# automaton.net
KiCad netlist of a schematic drawn in EAGLE
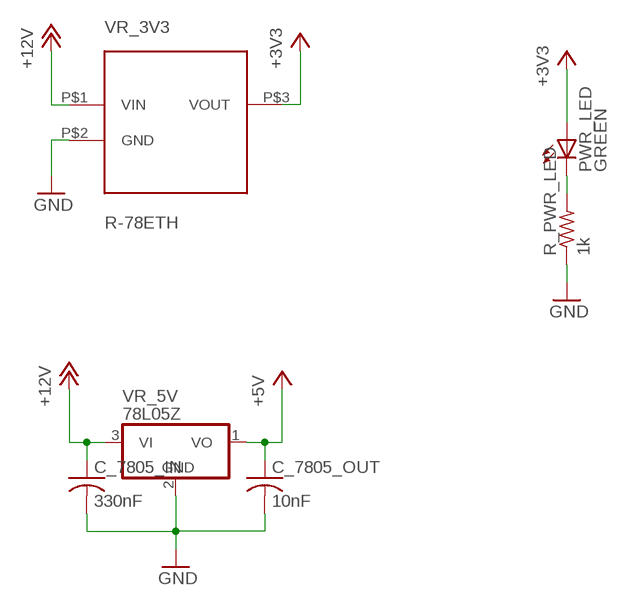
[diagram p0: schematic, sheet 1]
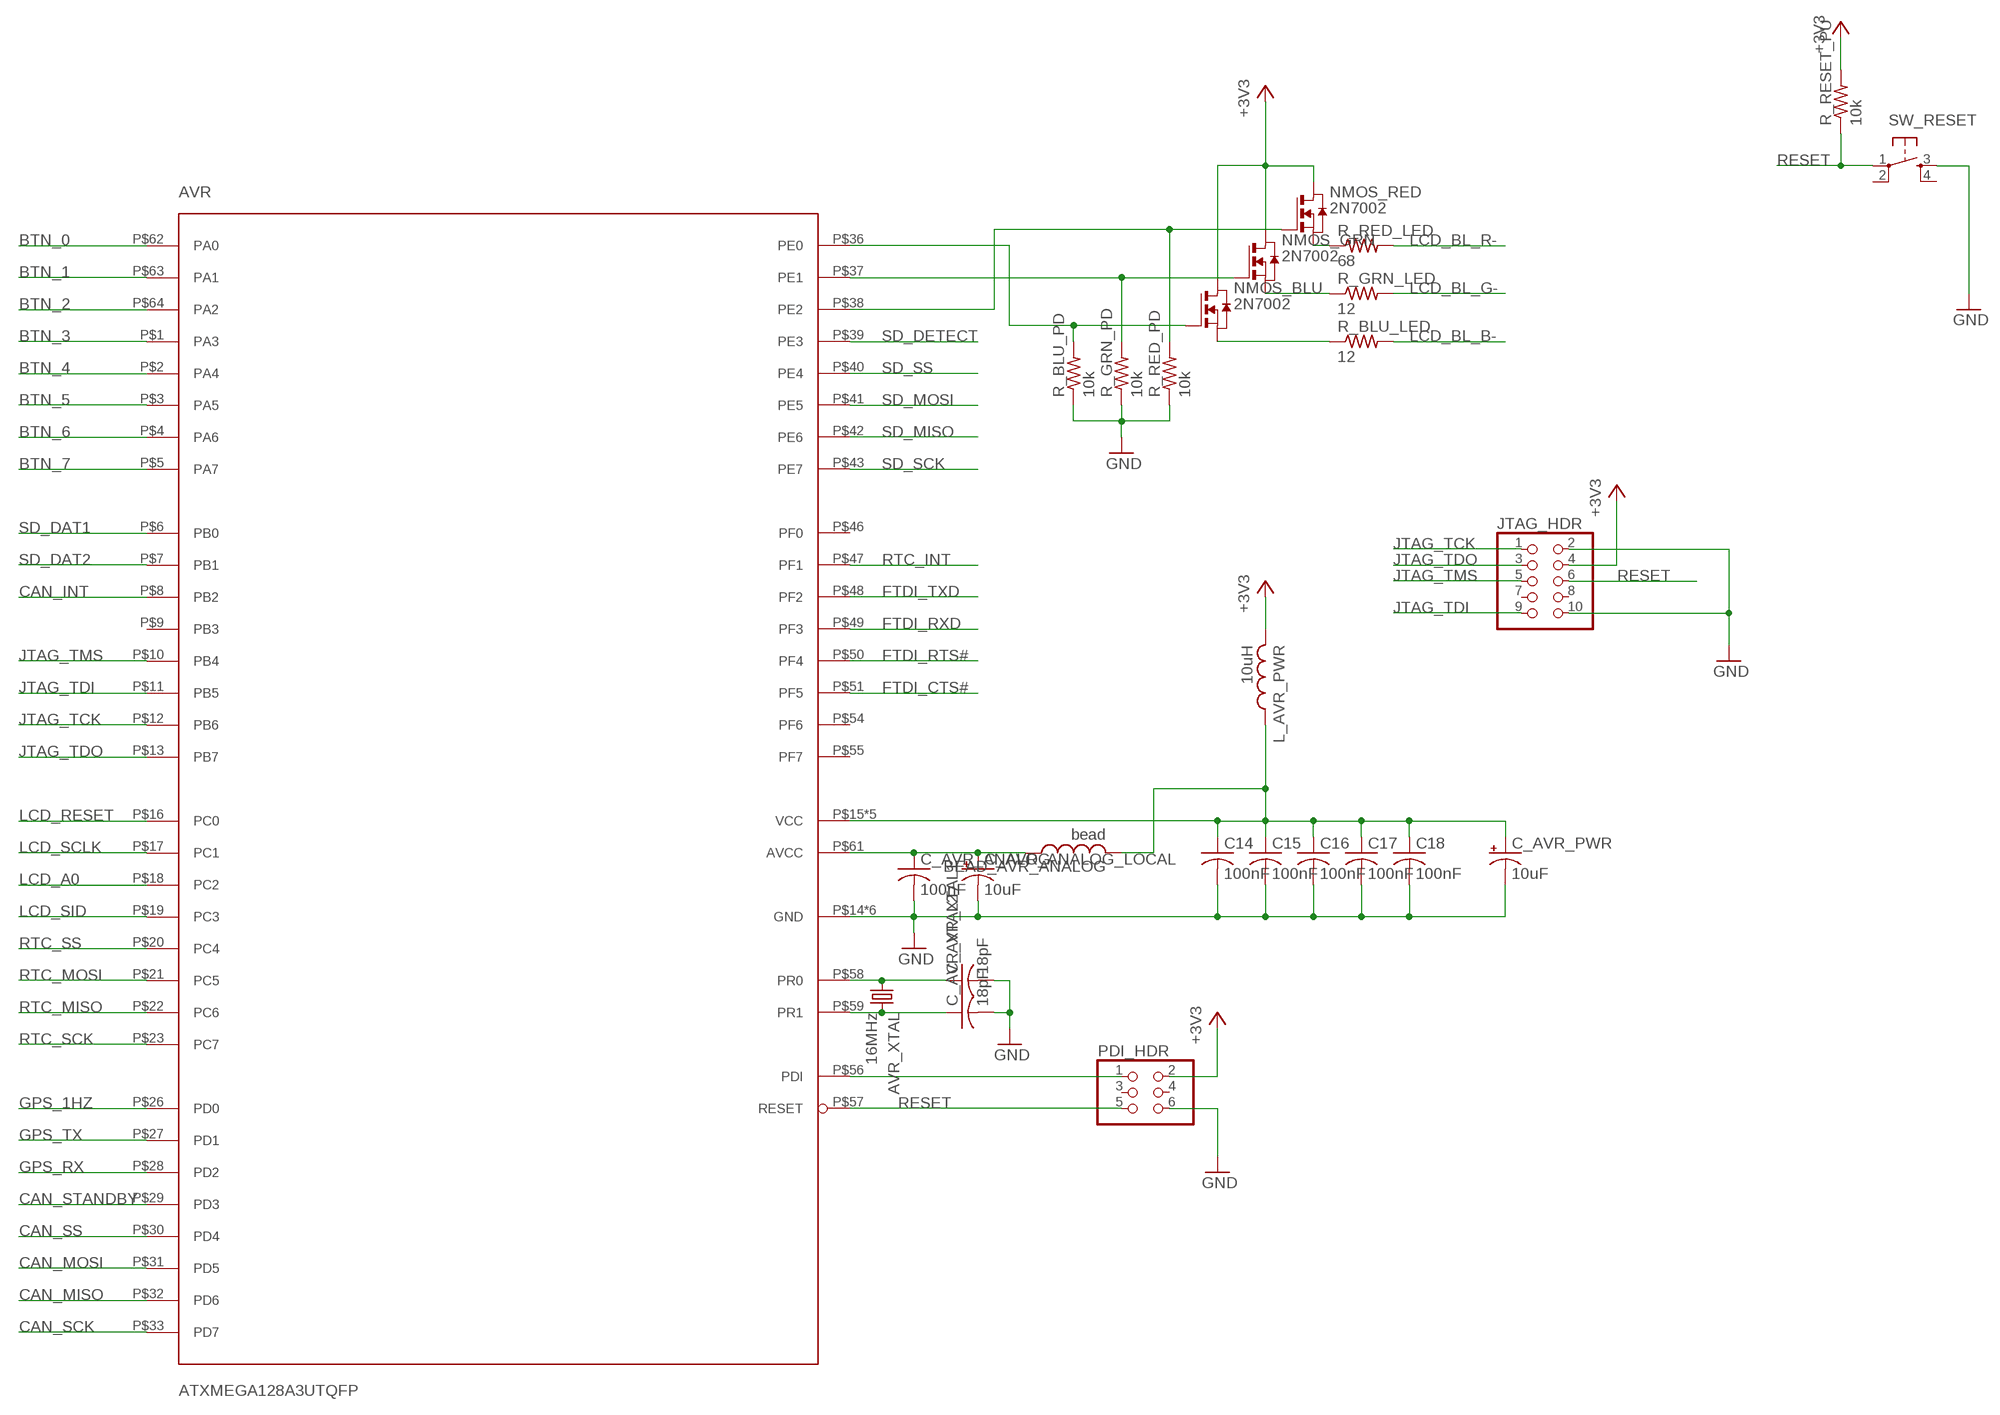
[diagram p1: schematic, sheet 2]
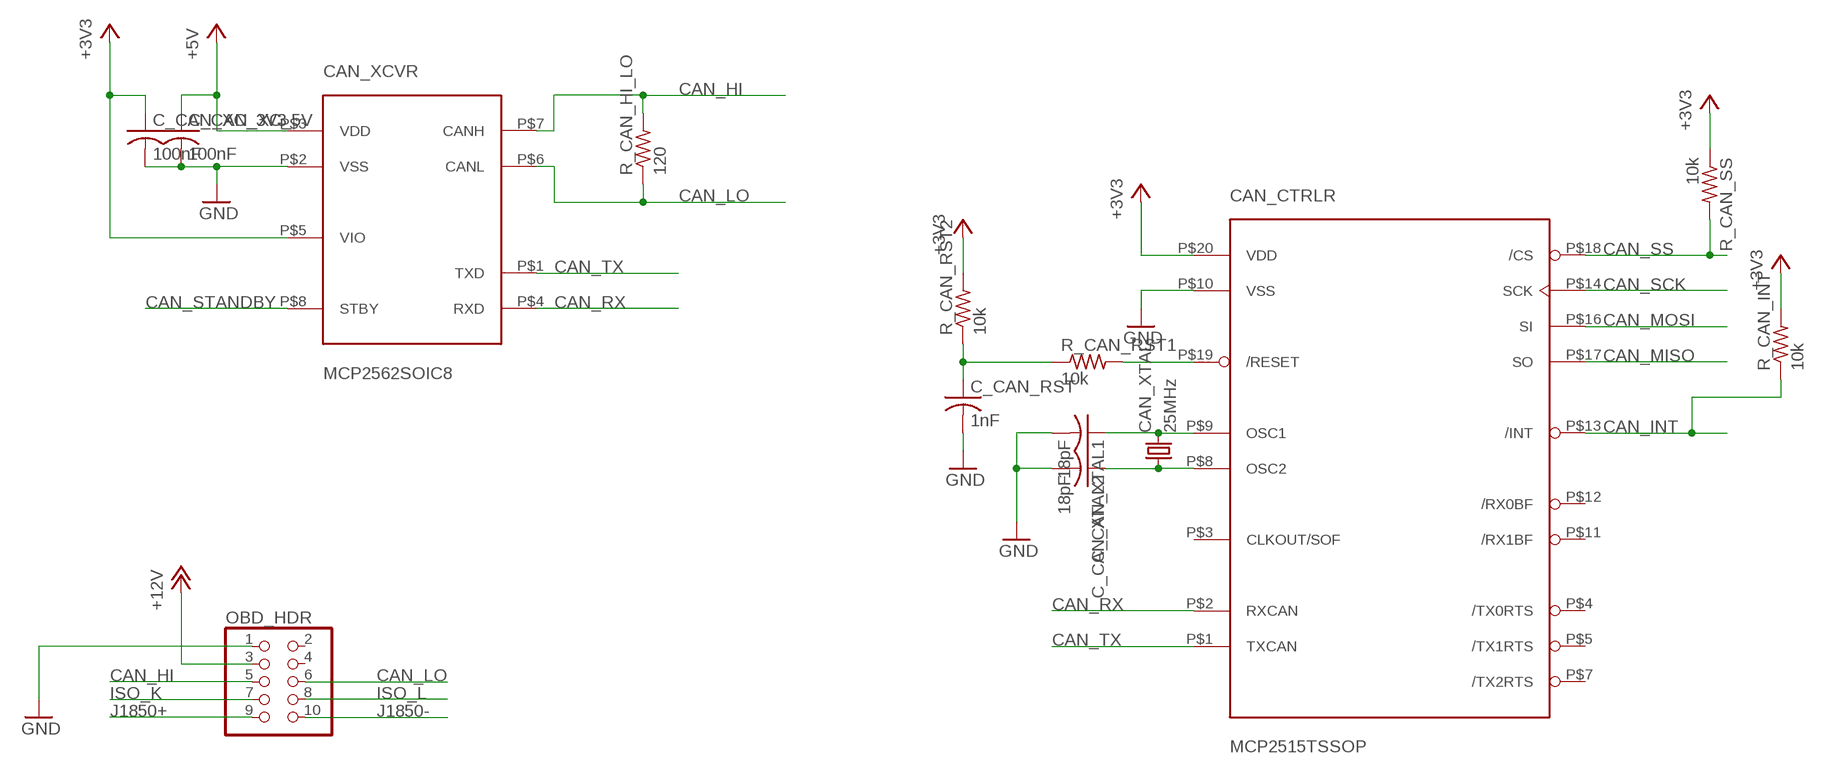
[diagram p2: schematic, sheet 3]
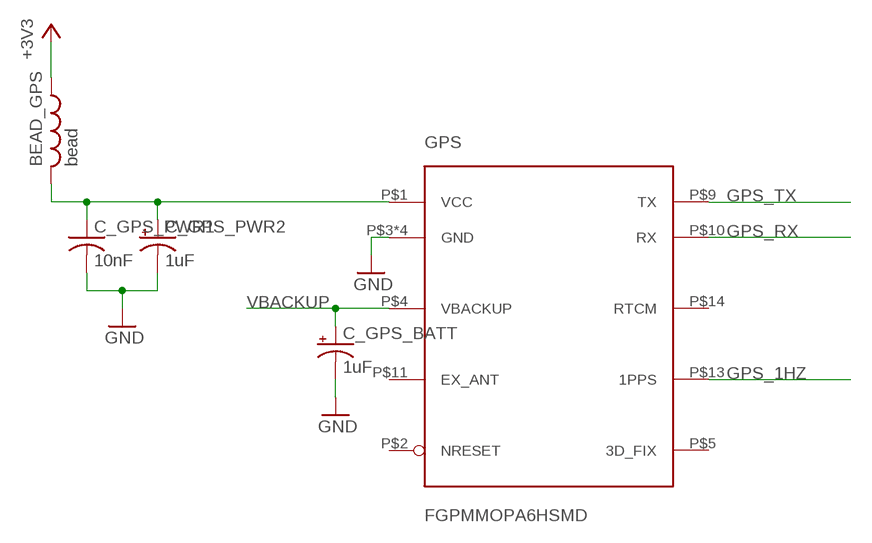
[diagram p3: schematic, sheet 4]
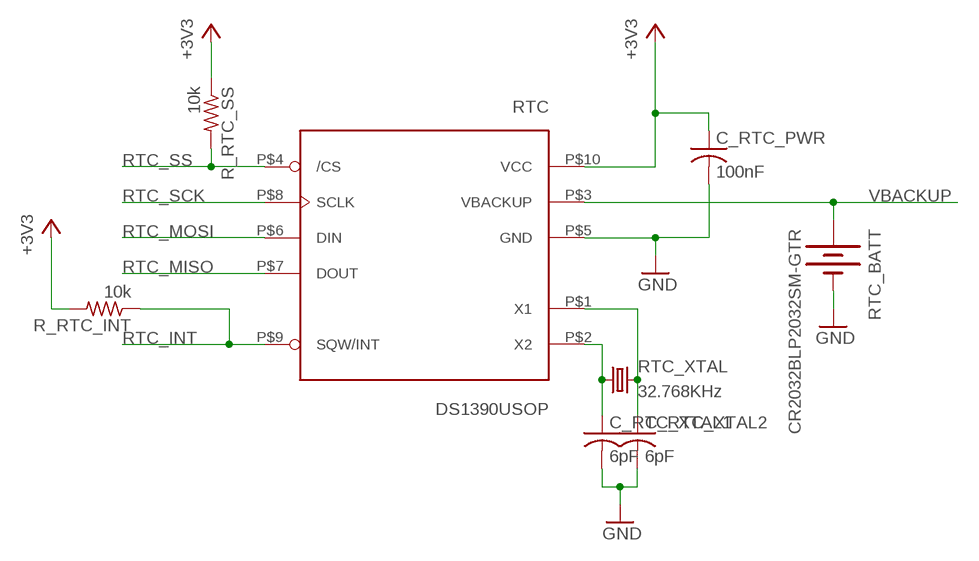
[diagram p4: schematic, sheet 5]
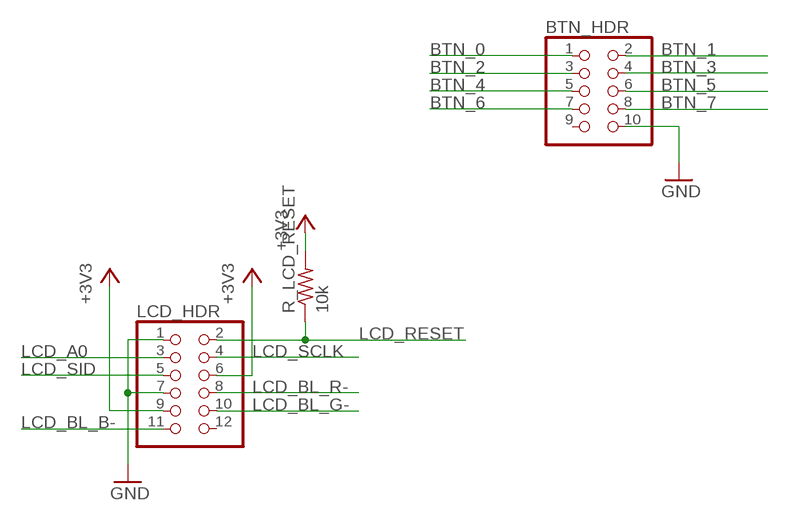
[diagram p5: schematic, sheet 6]
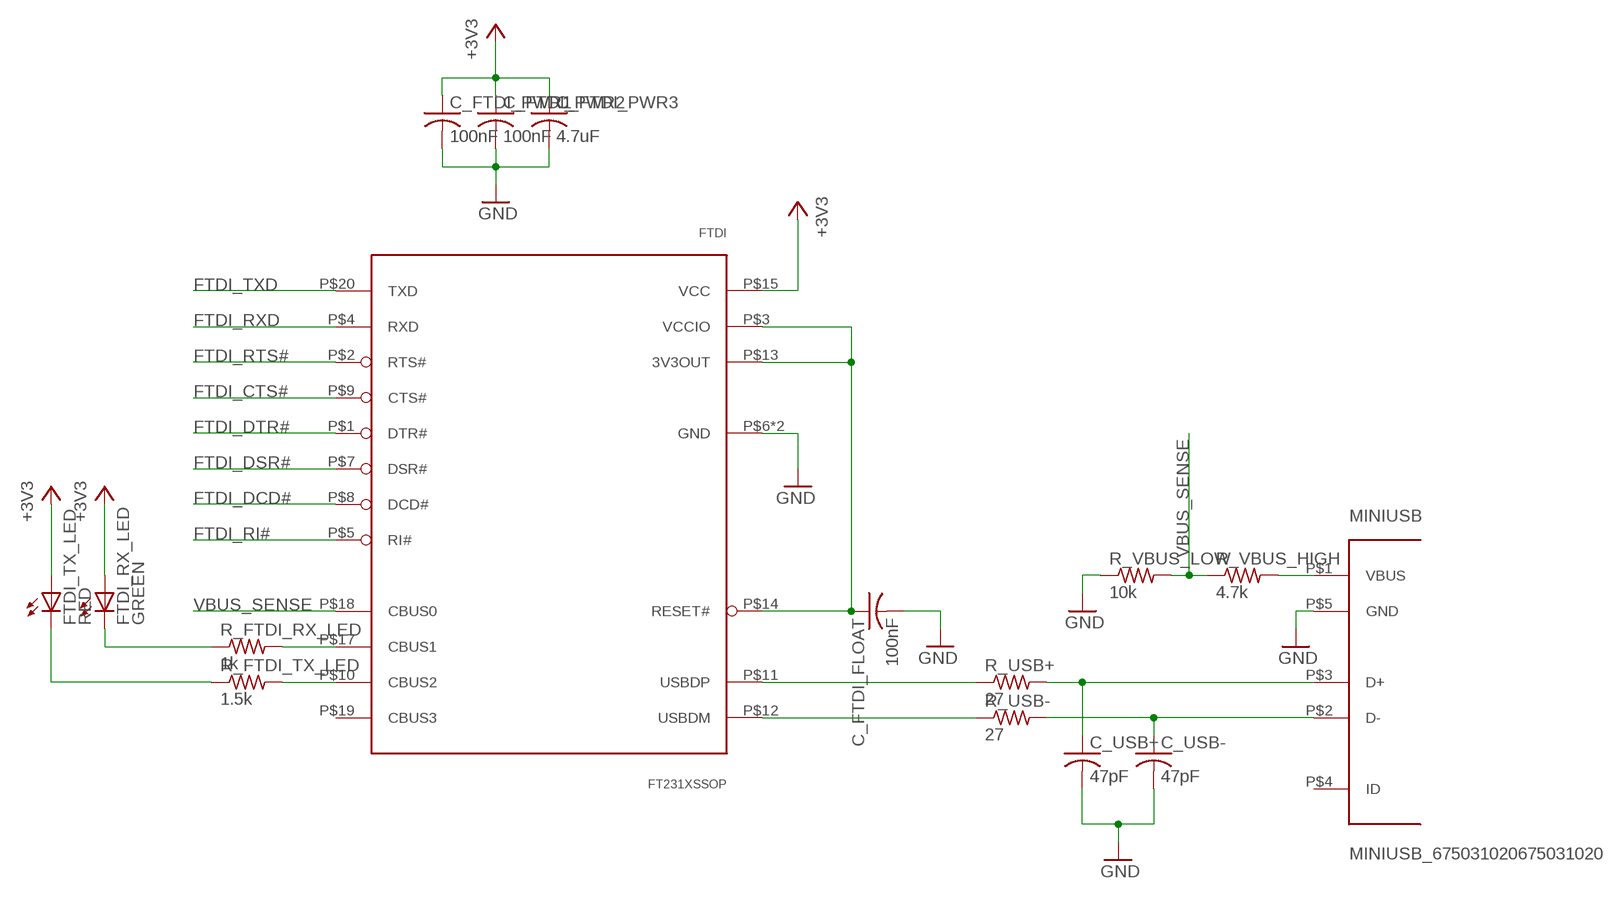
[diagram p6: schematic, sheet 7]
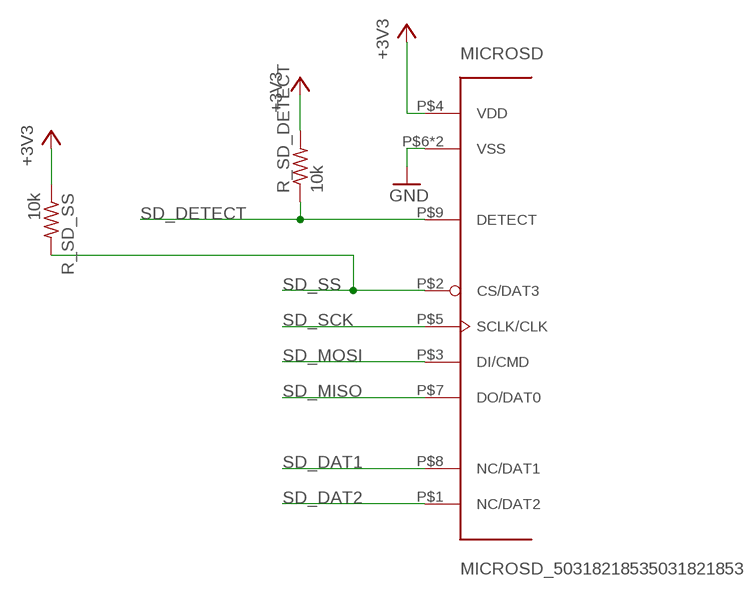
[diagram p7: schematic, sheet 8]

(export (version "E")
  (design (tool "Eeschema 10.0.6"))
  (components
    (comp (ref "MICROSD")
      (value "MICROSD_50318218535031821853")
      (footprint "eagle-import:MICROSD_5031821853")
      (libsource (lib "eagle-import") (part "MICROSD_50318218535031821853"))
    )
    (comp (ref "R_SD_DETECT")
      (value "10k")
      (footprint "eagle-import:R1206")
      (libsource (lib "eagle-import") (part "R-US_R1206"))
    )
    (comp (ref "R_SD_SS")
      (value "10k")
      (footprint "eagle-import:R1206")
      (libsource (lib "eagle-import") (part "R-US_R1206"))
    )
    (comp (ref "BEAD_GPS")
      (value "bead")
      (footprint "eagle-import:L1812")
      (libsource (lib "eagle-import") (part "L-USL1812"))
    )
    (comp (ref "C_GPS_BATT")
      (value "1uF")
      (footprint "eagle-import:E2-5")
      (libsource (lib "eagle-import") (part "CPOL-USE2-5"))
    )
    (comp (ref "C_GPS_PWR1")
      (value "10nF")
      (footprint "eagle-import:C1206")
      (libsource (lib "eagle-import") (part "C-USC1206"))
    )
    (comp (ref "C_GPS_PWR2")
      (value "1uF")
      (footprint "eagle-import:E2-5")
      (libsource (lib "eagle-import") (part "CPOL-USE2-5"))
    )
    (comp (ref "GPS")
      (value "FGPMMOPA6HSMD")
      (footprint "eagle-import:FGPMMOPA6H")
      (libsource (lib "eagle-import") (part "FGPMMOPA6HSMD"))
    )
    (comp (ref "AVR")
      (value "ATXMEGA128A3UTQFP")
      (footprint "eagle-import:ATMEL_TQFP64")
      (libsource (lib "eagle-import") (part "ATXMEGA128A3UTQFP"))
    )
    (comp (ref "AVR_XTAL")
      (value "16MHz")
      (footprint "eagle-import:HC49_S")
      (libsource (lib "eagle-import") (part "CRYSTALHC49S"))
    )
    (comp (ref "BEAD_AVR_ANALOG")
      (value "bead")
      (footprint "eagle-import:L1812")
      (libsource (lib "eagle-import") (part "L-USL1812"))
    )
    (comp (ref "C14")
      (value "100nF")
      (footprint "eagle-import:C1206")
      (libsource (lib "eagle-import") (part "C-USC1206"))
    )
    (comp (ref "C15")
      (value "100nF")
      (footprint "eagle-import:C1206")
      (libsource (lib "eagle-import") (part "C-USC1206"))
    )
    (comp (ref "C16")
      (value "100nF")
      (footprint "eagle-import:C1206")
      (libsource (lib "eagle-import") (part "C-USC1206"))
    )
    (comp (ref "C17")
      (value "100nF")
      (footprint "eagle-import:C1206")
      (libsource (lib "eagle-import") (part "C-USC1206"))
    )
    (comp (ref "C18")
      (value "100nF")
      (footprint "eagle-import:C1206")
      (libsource (lib "eagle-import") (part "C-USC1206"))
    )
    (comp (ref "C_AVR_ANALOG")
      (value "100nF")
      (footprint "eagle-import:C1206")
      (libsource (lib "eagle-import") (part "C-USC1206"))
    )
    (comp (ref "C_AVR_ANALOG_LOCAL")
      (value "10uF")
      (footprint "eagle-import:E2-5")
      (libsource (lib "eagle-import") (part "CPOL-USE2-5"))
    )
    (comp (ref "C_AVR_PWR")
      (value "10uF")
      (footprint "eagle-import:E2-5")
      (libsource (lib "eagle-import") (part "CPOL-USE2-5"))
    )
    (comp (ref "C_AVR_XTAL1")
      (value "18pF")
      (footprint "eagle-import:C1206")
      (libsource (lib "eagle-import") (part "C-USC1206"))
    )
    (comp (ref "C_AVR_XTAL2")
      (value "18pF")
      (footprint "eagle-import:C1206")
      (libsource (lib "eagle-import") (part "C-USC1206"))
    )
    (comp (ref "JTAG_HDR")
      (value "PINHD-2X05_2.54")
      (footprint "eagle-import:2X05")
      (libsource (lib "eagle-import") (part "PINHD-2X05_2.54"))
    )
    (comp (ref "L_AVR_PWR")
      (value "10uH")
      (footprint "eagle-import:L1812")
      (libsource (lib "eagle-import") (part "L-USL1812"))
    )
    (comp (ref "NMOS_BLU")
      (value "2N7002")
      (footprint "eagle-import:SOT-23")
      (libsource (lib "eagle-import") (part "NMOSSOT23"))
    )
    (comp (ref "NMOS_GRN")
      (value "2N7002")
      (footprint "eagle-import:SOT-23")
      (libsource (lib "eagle-import") (part "NMOSSOT23"))
    )
    (comp (ref "NMOS_RED")
      (value "2N7002")
      (footprint "eagle-import:SOT-23")
      (libsource (lib "eagle-import") (part "NMOSSOT23"))
    )
    (comp (ref "PDI_HDR")
      (value "PINHD-2X03_2.54")
      (footprint "eagle-import:2X03")
      (libsource (lib "eagle-import") (part "PINHD-2X03_2.54"))
    )
    (comp (ref "R_BLU_LED")
      (value "12")
      (footprint "eagle-import:R1206")
      (libsource (lib "eagle-import") (part "R-US_R1206"))
    )
    (comp (ref "R_BLU_PD")
      (value "10k")
      (footprint "eagle-import:R1206")
      (libsource (lib "eagle-import") (part "R-US_R1206"))
    )
    (comp (ref "R_GRN_LED")
      (value "12")
      (footprint "eagle-import:R1206")
      (libsource (lib "eagle-import") (part "R-US_R1206"))
    )
    (comp (ref "R_GRN_PD")
      (value "10k")
      (footprint "eagle-import:R1206")
      (libsource (lib "eagle-import") (part "R-US_R1206"))
    )
    (comp (ref "R_RED_LED")
      (value "68")
      (footprint "eagle-import:R1206")
      (libsource (lib "eagle-import") (part "R-US_R1206"))
    )
    (comp (ref "R_RED_PD")
      (value "10k")
      (footprint "eagle-import:R1206")
      (libsource (lib "eagle-import") (part "R-US_R1206"))
    )
    (comp (ref "R_RESET_PU")
      (value "10k")
      (footprint "eagle-import:R1206")
      (libsource (lib "eagle-import") (part "R-US_R1206"))
    )
    (comp (ref "SW_RESET")
      (value "TAC_SWITCHSMD")
      (footprint "eagle-import:TACTILE_SWITCH_SMD")
      (libsource (lib "eagle-import") (part "TAC_SWITCHSMD"))
    )
    (comp (ref "C_7805_IN")
      (value "330nF")
      (footprint "eagle-import:C1206")
      (libsource (lib "eagle-import") (part "C-USC1206"))
    )
    (comp (ref "C_7805_OUT")
      (value "10nF")
      (footprint "eagle-import:C1206")
      (libsource (lib "eagle-import") (part "C-USC1206"))
    )
    (comp (ref "PWR_LED")
      (value "GREEN")
      (footprint "eagle-import:CHIPLED_1206")
      (libsource (lib "eagle-import") (part "LEDCHIPLED_1206"))
    )
    (comp (ref "R_PWR_LED")
      (value "1k")
      (footprint "eagle-import:R1206")
      (libsource (lib "eagle-import") (part "R-US_R1206"))
    )
    (comp (ref "VR_3V3")
      (value "R-78ETH")
      (footprint "eagle-import:R-78E")
      (libsource (lib "eagle-import") (part "R-78ETH"))
    )
    (comp (ref "VR_5V")
      (value "78L05Z")
      (footprint "eagle-import:TO92")
      (libsource (lib "eagle-import") (part "78ZL05"))
    )
    (comp (ref "C_FTDI_FLOAT")
      (value "100nF")
      (footprint "eagle-import:C1206")
      (libsource (lib "eagle-import") (part "C-USC1206"))
    )
    (comp (ref "C_FTDI_PWR1")
      (value "100nF")
      (footprint "eagle-import:C1206")
      (libsource (lib "eagle-import") (part "C-USC1206"))
    )
    (comp (ref "C_FTDI_PWR2")
      (value "100nF")
      (footprint "eagle-import:C1206")
      (libsource (lib "eagle-import") (part "C-USC1206"))
    )
    (comp (ref "C_FTDI_PWR3")
      (value "4.7uF")
      (footprint "eagle-import:C1206")
      (libsource (lib "eagle-import") (part "C-USC1206"))
    )
    (comp (ref "C_USB+")
      (value "47pF")
      (footprint "eagle-import:C1206")
      (libsource (lib "eagle-import") (part "C-USC1206"))
    )
    (comp (ref "C_USB-")
      (value "47pF")
      (footprint "eagle-import:C1206")
      (libsource (lib "eagle-import") (part "C-USC1206"))
    )
    (comp (ref "FTDI")
      (value "FT231XSSOP")
      (footprint "eagle-import:FTDI_SSOP20")
      (libsource (lib "eagle-import") (part "FT231XSSOP"))
    )
    (comp (ref "FTDI_RX_LED")
      (value "GREEN")
      (footprint "eagle-import:CHIPLED_1206")
      (libsource (lib "eagle-import") (part "LEDCHIPLED_1206"))
    )
    (comp (ref "FTDI_TX_LED")
      (value "RED")
      (footprint "eagle-import:CHIPLED_1206")
      (libsource (lib "eagle-import") (part "LEDCHIPLED_1206"))
    )
    (comp (ref "MINIUSB")
      (value "MINIUSB_675031020675031020")
      (footprint "eagle-import:MINIUSB_675031020")
      (libsource (lib "eagle-import") (part "MINIUSB_675031020675031020"))
    )
    (comp (ref "R_FTDI_RX_LED")
      (value "1k")
      (footprint "eagle-import:R1206")
      (libsource (lib "eagle-import") (part "R-US_R1206"))
    )
    (comp (ref "R_FTDI_TX_LED")
      (value "1.5k")
      (footprint "eagle-import:R1206")
      (libsource (lib "eagle-import") (part "R-US_R1206"))
    )
    (comp (ref "R_USB+")
      (value "27")
      (footprint "eagle-import:R1206")
      (libsource (lib "eagle-import") (part "R-US_R1206"))
    )
    (comp (ref "R_USB-")
      (value "27")
      (footprint "eagle-import:R1206")
      (libsource (lib "eagle-import") (part "R-US_R1206"))
    )
    (comp (ref "R_VBUS_HIGH")
      (value "4.7k")
      (footprint "eagle-import:R1206")
      (libsource (lib "eagle-import") (part "R-US_R1206"))
    )
    (comp (ref "R_VBUS_LOW")
      (value "10k")
      (footprint "eagle-import:R1206")
      (libsource (lib "eagle-import") (part "R-US_R1206"))
    )
    (comp (ref "C_RTC_PWR")
      (value "100nF")
      (footprint "eagle-import:C1206")
      (libsource (lib "eagle-import") (part "C-USC1206"))
    )
    (comp (ref "C_RTC_XTAL1")
      (value "6pF")
      (footprint "eagle-import:C1206")
      (libsource (lib "eagle-import") (part "C-USC1206"))
    )
    (comp (ref "C_RTC_XTAL2")
      (value "6pF")
      (footprint "eagle-import:C1206")
      (libsource (lib "eagle-import") (part "C-USC1206"))
    )
    (comp (ref "RTC")
      (value "DS1390USOP")
      (footprint "eagle-import:MAXIM_10USOP")
      (libsource (lib "eagle-import") (part "DS1390USOP"))
    )
    (comp (ref "RTC_BATT")
      (value "CR2032BLP2032SM-GTR")
      (footprint "eagle-import:BLP2032SM-GTR")
      (libsource (lib "eagle-import") (part "CR2032BLP2032SM-GTR"))
    )
    (comp (ref "RTC_XTAL")
      (value "32.768KHz")
      (footprint "eagle-import:TC26V")
      (libsource (lib "eagle-import") (part "CRYSTALTC26V"))
    )
    (comp (ref "R_RTC_INT")
      (value "10k")
      (footprint "eagle-import:R1206")
      (libsource (lib "eagle-import") (part "R-US_R1206"))
    )
    (comp (ref "R_RTC_SS")
      (value "10k")
      (footprint "eagle-import:R1206")
      (libsource (lib "eagle-import") (part "R-US_R1206"))
    )
    (comp (ref "CAN_CTRLR")
      (value "MCP2515TSSOP")
      (footprint "eagle-import:MICROCHIP_TSSOP20")
      (libsource (lib "eagle-import") (part "MCP2515TSSOP"))
    )
    (comp (ref "CAN_XCVR")
      (value "MCP2562SOIC8")
      (footprint "eagle-import:MICROCHIP_SOIC8")
      (libsource (lib "eagle-import") (part "MCP2562SOIC8"))
    )
    (comp (ref "CAN_XTAL")
      (value "25MHz")
      (footprint "eagle-import:HC49_S")
      (libsource (lib "eagle-import") (part "CRYSTALHC49S"))
    )
    (comp (ref "C_CAN_RST")
      (value "1nF")
      (footprint "eagle-import:C1206")
      (libsource (lib "eagle-import") (part "C-USC1206"))
    )
    (comp (ref "C_CAN_XC_3V3")
      (value "100nF")
      (footprint "eagle-import:C1206")
      (libsource (lib "eagle-import") (part "C-USC1206"))
    )
    (comp (ref "C_CAN_XC_5V")
      (value "100nF")
      (footprint "eagle-import:C1206")
      (libsource (lib "eagle-import") (part "C-USC1206"))
    )
    (comp (ref "C_CAN_XTAL1")
      (value "18pF")
      (footprint "eagle-import:C1206")
      (libsource (lib "eagle-import") (part "C-USC1206"))
    )
    (comp (ref "C_CAN_XTAL2")
      (value "18pF")
      (footprint "eagle-import:C1206")
      (libsource (lib "eagle-import") (part "C-USC1206"))
    )
    (comp (ref "OBD_HDR")
      (value "PINHD-2X05_2.54-90°")
      (footprint "eagle-import:2X05_90")
      (libsource (lib "eagle-import") (part "PINHD-2X05_2.54-90°"))
    )
    (comp (ref "R_CAN_HI_LO")
      (value "120")
      (footprint "eagle-import:R1206")
      (libsource (lib "eagle-import") (part "R-US_R1206"))
    )
    (comp (ref "R_CAN_INT")
      (value "10k")
      (footprint "eagle-import:R1206")
      (libsource (lib "eagle-import") (part "R-US_R1206"))
    )
    (comp (ref "R_CAN_RST1")
      (value "10k")
      (footprint "eagle-import:R1206")
      (libsource (lib "eagle-import") (part "R-US_R1206"))
    )
    (comp (ref "R_CAN_RST2")
      (value "10k")
      (footprint "eagle-import:R1206")
      (libsource (lib "eagle-import") (part "R-US_R1206"))
    )
    (comp (ref "R_CAN_SS")
      (value "10k")
      (footprint "eagle-import:R1206")
      (libsource (lib "eagle-import") (part "R-US_R1206"))
    )
    (comp (ref "BTN_HDR")
      (value "PINHD-2X05_2.54")
      (footprint "eagle-import:2X05")
      (libsource (lib "eagle-import") (part "PINHD-2X05_2.54"))
    )
    (comp (ref "LCD_HDR")
      (value "PINHD-2X06_2.54")
      (footprint "eagle-import:2X06")
      (libsource (lib "eagle-import") (part "PINHD-2X06_2.54"))
    )
    (comp (ref "R_LCD_RESET")
      (value "10k")
      (footprint "eagle-import:R1206")
      (libsource (lib "eagle-import") (part "R-US_R1206"))
    )
  )
  (nets
    (net (code "1") (name "+3V3") (class "Default")
      (node (ref "BEAD_GPS") (pin "1") (pinfunction "1_1") (pintype "passive"))
      (node (ref "CAN_CTRLR") (pin "P$20") (pinfunction "VDD_P$20") (pintype "power_in"))
      (node (ref "CAN_XCVR") (pin "P$5") (pinfunction "VIO_P$5") (pintype "power_in"))
      (node (ref "C_CAN_XC_3V3") (pin "1") (pinfunction "1_1") (pintype "passive"))
      (node (ref "C_FTDI_PWR1") (pin "1") (pinfunction "1_1") (pintype "passive"))
      (node (ref "C_FTDI_PWR2") (pin "1") (pinfunction "1_1") (pintype "passive"))
      (node (ref "C_FTDI_PWR3") (pin "1") (pinfunction "1_1") (pintype "passive"))
      (node (ref "C_RTC_PWR") (pin "1") (pinfunction "1_1") (pintype "passive"))
      (node (ref "FTDI") (pin "P$15") (pinfunction "VCC_P$15") (pintype "power_in"))
      (node (ref "FTDI_RX_LED") (pin "A") (pinfunction "A_A") (pintype "passive"))
      (node (ref "FTDI_TX_LED") (pin "A") (pinfunction "A_A") (pintype "passive"))
      (node (ref "JTAG_HDR") (pin "4") (pinfunction "4_4") (pintype "passive"))
      (node (ref "LCD_HDR") (pin "6") (pinfunction "6_6") (pintype "passive"))
      (node (ref "LCD_HDR") (pin "9") (pinfunction "9_9") (pintype "passive"))
      (node (ref "L_AVR_PWR") (pin "2") (pinfunction "2_2") (pintype "passive"))
      (node (ref "MICROSD") (pin "P$4") (pinfunction "VDD_P$4") (pintype "power_in"))
      (node (ref "NMOS_BLU") (pin "1") (pinfunction "D_1") (pintype "passive"))
      (node (ref "NMOS_GRN") (pin "1") (pinfunction "D_1") (pintype "passive"))
      (node (ref "NMOS_RED") (pin "1") (pinfunction "D_1") (pintype "passive"))
      (node (ref "PDI_HDR") (pin "2") (pinfunction "2_2") (pintype "passive"))
      (node (ref "PWR_LED") (pin "A") (pinfunction "A_A") (pintype "passive"))
      (node (ref "RTC") (pin "P$10") (pinfunction "VCC_P$10") (pintype "power_in"))
      (node (ref "R_CAN_INT") (pin "2") (pinfunction "2_2") (pintype "passive"))
      (node (ref "R_CAN_RST2") (pin "2") (pinfunction "2_2") (pintype "passive"))
      (node (ref "R_CAN_SS") (pin "1") (pinfunction "1_1") (pintype "passive"))
      (node (ref "R_LCD_RESET") (pin "2") (pinfunction "2_2") (pintype "passive"))
      (node (ref "R_RESET_PU") (pin "2") (pinfunction "2_2") (pintype "passive"))
      (node (ref "R_RTC_INT") (pin "2") (pinfunction "2_2") (pintype "passive"))
      (node (ref "R_RTC_SS") (pin "1") (pinfunction "1_1") (pintype "passive"))
      (node (ref "R_SD_DETECT") (pin "2") (pinfunction "2_2") (pintype "passive"))
      (node (ref "R_SD_SS") (pin "1") (pinfunction "1_1") (pintype "passive"))
      (node (ref "VR_3V3") (pin "P$3") (pinfunction "VOUT_P$3") (pintype "power_in"))
    )
    (net (code "2") (name "+5V") (class "Default")
      (node (ref "CAN_XCVR") (pin "P$3") (pinfunction "VDD_P$3") (pintype "power_in"))
      (node (ref "C_7805_OUT") (pin "1") (pinfunction "1_1") (pintype "passive"))
      (node (ref "C_CAN_XC_5V") (pin "1") (pinfunction "1_1") (pintype "passive"))
      (node (ref "VR_5V") (pin "1") (pinfunction "VO_1") (pintype "passive"))
    )
    (net (code "3") (name "+12V") (class "Default")
      (node (ref "C_7805_IN") (pin "1") (pinfunction "1_1") (pintype "passive"))
      (node (ref "OBD_HDR") (pin "3") (pinfunction "3_3") (pintype "passive"))
      (node (ref "VR_3V3") (pin "P$1") (pinfunction "VIN_P$1") (pintype "power_in"))
      (node (ref "VR_5V") (pin "3") (pinfunction "VI_3") (pintype "input"))
    )
    (net (code "4") (name "BTN_0") (class "Default")
      (node (ref "AVR") (pin "P$62") (pinfunction "PA0_P$62") (pintype "bidirectional"))
      (node (ref "BTN_HDR") (pin "1") (pinfunction "1_1") (pintype "passive"))
    )
    (net (code "5") (name "BTN_1") (class "Default")
      (node (ref "AVR") (pin "P$63") (pinfunction "PA1_P$63") (pintype "bidirectional"))
      (node (ref "BTN_HDR") (pin "2") (pinfunction "2_2") (pintype "passive"))
    )
    (net (code "6") (name "BTN_2") (class "Default")
      (node (ref "AVR") (pin "P$64") (pinfunction "PA2_P$64") (pintype "bidirectional"))
      (node (ref "BTN_HDR") (pin "3") (pinfunction "3_3") (pintype "passive"))
    )
    (net (code "7") (name "BTN_3") (class "Default")
      (node (ref "AVR") (pin "P$1") (pinfunction "PA3_P$1") (pintype "bidirectional"))
      (node (ref "BTN_HDR") (pin "4") (pinfunction "4_4") (pintype "passive"))
    )
    (net (code "8") (name "BTN_4") (class "Default")
      (node (ref "AVR") (pin "P$2") (pinfunction "PA4_P$2") (pintype "bidirectional"))
      (node (ref "BTN_HDR") (pin "5") (pinfunction "5_5") (pintype "passive"))
    )
    (net (code "9") (name "BTN_5") (class "Default")
      (node (ref "AVR") (pin "P$3") (pinfunction "PA5_P$3") (pintype "bidirectional"))
      (node (ref "BTN_HDR") (pin "6") (pinfunction "6_6") (pintype "passive"))
    )
    (net (code "10") (name "BTN_6") (class "Default")
      (node (ref "AVR") (pin "P$4") (pinfunction "PA6_P$4") (pintype "bidirectional"))
      (node (ref "BTN_HDR") (pin "7") (pinfunction "7_7") (pintype "passive"))
    )
    (net (code "11") (name "BTN_7") (class "Default")
      (node (ref "AVR") (pin "P$5") (pinfunction "PA7_P$5") (pintype "bidirectional"))
      (node (ref "BTN_HDR") (pin "8") (pinfunction "8_8") (pintype "passive"))
    )
    (net (code "12") (name "CAN_HI") (class "Default")
      (node (ref "CAN_XCVR") (pin "P$7") (pinfunction "CANH_P$7") (pintype "bidirectional"))
      (node (ref "OBD_HDR") (pin "5") (pinfunction "5_5") (pintype "passive"))
      (node (ref "R_CAN_HI_LO") (pin "2") (pinfunction "2_2") (pintype "passive"))
    )
    (net (code "13") (name "CAN_INT") (class "Default")
      (node (ref "AVR") (pin "P$8") (pinfunction "PB2_P$8") (pintype "bidirectional"))
      (node (ref "CAN_CTRLR") (pin "P$13") (pinfunction "/INT_P$13") (pintype "bidirectional"))
      (node (ref "R_CAN_INT") (pin "1") (pinfunction "1_1") (pintype "passive"))
    )
    (net (code "14") (name "CAN_LO") (class "Default")
      (node (ref "CAN_XCVR") (pin "P$6") (pinfunction "CANL_P$6") (pintype "bidirectional"))
      (node (ref "OBD_HDR") (pin "6") (pinfunction "6_6") (pintype "passive"))
      (node (ref "R_CAN_HI_LO") (pin "1") (pinfunction "1_1") (pintype "passive"))
    )
    (net (code "15") (name "CAN_MISO") (class "Default")
      (node (ref "AVR") (pin "P$32") (pinfunction "PD6_P$32") (pintype "bidirectional"))
      (node (ref "CAN_CTRLR") (pin "P$17") (pinfunction "SO_P$17") (pintype "output"))
    )
    (net (code "16") (name "CAN_MOSI") (class "Default")
      (node (ref "AVR") (pin "P$31") (pinfunction "PD5_P$31") (pintype "bidirectional"))
      (node (ref "CAN_CTRLR") (pin "P$16") (pinfunction "SI_P$16") (pintype "input"))
    )
    (net (code "17") (name "CAN_RX") (class "Default")
      (node (ref "CAN_CTRLR") (pin "P$2") (pinfunction "RXCAN_P$2") (pintype "input"))
      (node (ref "CAN_XCVR") (pin "P$4") (pinfunction "RXD_P$4") (pintype "output"))
    )
    (net (code "18") (name "CAN_SCK") (class "Default")
      (node (ref "AVR") (pin "P$33") (pinfunction "PD7_P$33") (pintype "bidirectional"))
      (node (ref "CAN_CTRLR") (pin "P$14") (pinfunction "SCK_P$14") (pintype "input"))
    )
    (net (code "19") (name "CAN_SS") (class "Default")
      (node (ref "AVR") (pin "P$30") (pinfunction "PD4_P$30") (pintype "bidirectional"))
      (node (ref "CAN_CTRLR") (pin "P$18") (pinfunction "/CS_P$18") (pintype "input"))
      (node (ref "R_CAN_SS") (pin "2") (pinfunction "2_2") (pintype "passive"))
    )
    (net (code "20") (name "CAN_STANDBY") (class "Default")
      (node (ref "AVR") (pin "P$29") (pinfunction "PD3_P$29") (pintype "bidirectional"))
      (node (ref "CAN_XCVR") (pin "P$8") (pinfunction "STBY_P$8") (pintype "bidirectional"))
    )
    (net (code "21") (name "CAN_TX") (class "Default")
      (node (ref "CAN_CTRLR") (pin "P$1") (pinfunction "TXCAN_P$1") (pintype "output"))
      (node (ref "CAN_XCVR") (pin "P$1") (pinfunction "TXD_P$1") (pintype "input"))
    )
    (net (code "22") (name "FTDI_CTS#") (class "Default")
      (node (ref "AVR") (pin "P$51") (pinfunction "PF5_P$51") (pintype "bidirectional"))
      (node (ref "FTDI") (pin "P$9") (pinfunction "CTS#_P$9") (pintype "bidirectional"))
    )
    (net (code "23") (name "FTDI_DCD#") (class "Default")
      (node (ref "FTDI") (pin "P$8") (pinfunction "DCD#_P$8") (pintype "bidirectional"))
    )
    (net (code "24") (name "FTDI_DSR#") (class "Default")
      (node (ref "FTDI") (pin "P$7") (pinfunction "DSR#_P$7") (pintype "bidirectional"))
    )
    (net (code "25") (name "FTDI_DTR#") (class "Default")
      (node (ref "FTDI") (pin "P$1") (pinfunction "DTR#_P$1") (pintype "bidirectional"))
    )
    (net (code "26") (name "FTDI_RI#") (class "Default")
      (node (ref "FTDI") (pin "P$5") (pinfunction "RI#_P$5") (pintype "bidirectional"))
    )
    (net (code "27") (name "FTDI_RTS#") (class "Default")
      (node (ref "AVR") (pin "P$50") (pinfunction "PF4_P$50") (pintype "bidirectional"))
      (node (ref "FTDI") (pin "P$2") (pinfunction "RTS#_P$2") (pintype "bidirectional"))
    )
    (net (code "28") (name "FTDI_RXD") (class "Default")
      (node (ref "AVR") (pin "P$49") (pinfunction "PF3_P$49") (pintype "bidirectional"))
      (node (ref "FTDI") (pin "P$4") (pinfunction "RXD_P$4") (pintype "input"))
    )
    (net (code "29") (name "FTDI_TXD") (class "Default")
      (node (ref "AVR") (pin "P$48") (pinfunction "PF2_P$48") (pintype "bidirectional"))
      (node (ref "FTDI") (pin "P$20") (pinfunction "TXD_P$20") (pintype "output"))
    )
    (net (code "30") (name "GND") (class "Default")
      (node (ref "AVR") (pin "P$14") (pinfunction "GND_P$14") (pintype "power_in"))
      (node (ref "AVR") (pin "P$24") (pinfunction "GND_P$24") (pintype "power_in"))
      (node (ref "AVR") (pin "P$34") (pinfunction "GND_P$34") (pintype "power_in"))
      (node (ref "AVR") (pin "P$44") (pinfunction "GND_P$44") (pintype "power_in"))
      (node (ref "AVR") (pin "P$52") (pinfunction "GND_P$52") (pintype "power_in"))
      (node (ref "AVR") (pin "P$60") (pinfunction "GND_P$60") (pintype "power_in"))
      (node (ref "BTN_HDR") (pin "10") (pinfunction "10_10") (pintype "passive"))
      (node (ref "C14") (pin "2") (pinfunction "2_2") (pintype "passive"))
      (node (ref "C15") (pin "2") (pinfunction "2_2") (pintype "passive"))
      (node (ref "C16") (pin "2") (pinfunction "2_2") (pintype "passive"))
      (node (ref "C17") (pin "2") (pinfunction "2_2") (pintype "passive"))
      (node (ref "C18") (pin "2") (pinfunction "2_2") (pintype "passive"))
      (node (ref "CAN_CTRLR") (pin "P$10") (pinfunction "VSS_P$10") (pintype "power_in"))
      (node (ref "CAN_XCVR") (pin "P$2") (pinfunction "VSS_P$2") (pintype "power_in"))
      (node (ref "C_7805_IN") (pin "2") (pinfunction "2_2") (pintype "passive"))
      (node (ref "C_7805_OUT") (pin "2") (pinfunction "2_2") (pintype "passive"))
      (node (ref "C_AVR_ANALOG") (pin "2") (pinfunction "2_2") (pintype "passive"))
      (node (ref "C_AVR_ANALOG_LOCAL") (pin "-") (pinfunction "-_-") (pintype "passive"))
      (node (ref "C_AVR_PWR") (pin "-") (pinfunction "-_-") (pintype "passive"))
      (node (ref "C_AVR_XTAL1") (pin "2") (pinfunction "2_2") (pintype "passive"))
      (node (ref "C_AVR_XTAL2") (pin "2") (pinfunction "2_2") (pintype "passive"))
      (node (ref "C_CAN_RST") (pin "2") (pinfunction "2_2") (pintype "passive"))
      (node (ref "C_CAN_XC_3V3") (pin "2") (pinfunction "2_2") (pintype "passive"))
      (node (ref "C_CAN_XC_5V") (pin "2") (pinfunction "2_2") (pintype "passive"))
      (node (ref "C_CAN_XTAL1") (pin "2") (pinfunction "2_2") (pintype "passive"))
      (node (ref "C_CAN_XTAL2") (pin "2") (pinfunction "2_2") (pintype "passive"))
      (node (ref "C_FTDI_FLOAT") (pin "2") (pinfunction "2_2") (pintype "passive"))
      (node (ref "C_FTDI_PWR1") (pin "2") (pinfunction "2_2") (pintype "passive"))
      (node (ref "C_FTDI_PWR2") (pin "2") (pinfunction "2_2") (pintype "passive"))
      (node (ref "C_FTDI_PWR3") (pin "2") (pinfunction "2_2") (pintype "passive"))
      (node (ref "C_GPS_BATT") (pin "-") (pinfunction "-_-") (pintype "passive"))
      (node (ref "C_GPS_PWR1") (pin "2") (pinfunction "2_2") (pintype "passive"))
      (node (ref "C_GPS_PWR2") (pin "-") (pinfunction "-_-") (pintype "passive"))
      (node (ref "C_RTC_PWR") (pin "2") (pinfunction "2_2") (pintype "passive"))
      (node (ref "C_RTC_XTAL1") (pin "2") (pinfunction "2_2") (pintype "passive"))
      (node (ref "C_RTC_XTAL2") (pin "2") (pinfunction "2_2") (pintype "passive"))
      (node (ref "C_USB+") (pin "2") (pinfunction "2_2") (pintype "passive"))
      (node (ref "C_USB-") (pin "2") (pinfunction "2_2") (pintype "passive"))
      (node (ref "FTDI") (pin "P$16") (pinfunction "GND_P$16") (pintype "power_in"))
      (node (ref "FTDI") (pin "P$6") (pinfunction "GND_P$6") (pintype "power_in"))
      (node (ref "GPS") (pin "P$12") (pinfunction "GND_P$12") (pintype "power_in"))
      (node (ref "GPS") (pin "P$19") (pinfunction "GND_P$19") (pintype "power_in"))
      (node (ref "GPS") (pin "P$3") (pinfunction "GND_P$3") (pintype "power_in"))
      (node (ref "GPS") (pin "P$8") (pinfunction "GND_P$8") (pintype "power_in"))
      (node (ref "JTAG_HDR") (pin "10") (pinfunction "10_10") (pintype "passive"))
      (node (ref "JTAG_HDR") (pin "2") (pinfunction "2_2") (pintype "passive"))
      (node (ref "LCD_HDR") (pin "1") (pinfunction "1_1") (pintype "passive"))
      (node (ref "LCD_HDR") (pin "7") (pinfunction "7_7") (pintype "passive"))
      (node (ref "MICROSD") (pin "P$10") (pinfunction "VSS_P$10") (pintype "power_in"))
      (node (ref "MICROSD") (pin "P$6") (pinfunction "VSS_P$6") (pintype "power_in"))
      (node (ref "MINIUSB") (pin "P$5") (pinfunction "GND_P$5") (pintype "power_in"))
      (node (ref "OBD_HDR") (pin "1") (pinfunction "1_1") (pintype "passive"))
      (node (ref "PDI_HDR") (pin "6") (pinfunction "6_6") (pintype "passive"))
      (node (ref "RTC") (pin "P$5") (pinfunction "GND_P$5") (pintype "power_in"))
      (node (ref "RTC_BATT") (pin "P$2") (pinfunction "-_P$2") (pintype "power_in"))
      (node (ref "R_BLU_PD") (pin "1") (pinfunction "1_1") (pintype "passive"))
      (node (ref "R_GRN_PD") (pin "1") (pinfunction "1_1") (pintype "passive"))
      (node (ref "R_PWR_LED") (pin "1") (pinfunction "1_1") (pintype "passive"))
      (node (ref "R_RED_PD") (pin "1") (pinfunction "1_1") (pintype "passive"))
      (node (ref "R_VBUS_LOW") (pin "1") (pinfunction "1_1") (pintype "passive"))
      (node (ref "SW_RESET") (pin "3") (pinfunction "3_3") (pintype "passive"))
      (node (ref "VR_3V3") (pin "P$2") (pinfunction "GND_P$2") (pintype "power_in"))
      (node (ref "VR_5V") (pin "2") (pinfunction "GND_2") (pintype "passive"))
    )
    (net (code "31") (name "GPS_1HZ") (class "Default")
      (node (ref "AVR") (pin "P$26") (pinfunction "PD0_P$26") (pintype "bidirectional"))
      (node (ref "GPS") (pin "P$13") (pinfunction "1PPS_P$13") (pintype "bidirectional"))
    )
    (net (code "32") (name "GPS_RX") (class "Default")
      (node (ref "AVR") (pin "P$28") (pinfunction "PD2_P$28") (pintype "bidirectional"))
      (node (ref "GPS") (pin "P$10") (pinfunction "RX_P$10") (pintype "input"))
    )
    (net (code "33") (name "GPS_TX") (class "Default")
      (node (ref "AVR") (pin "P$27") (pinfunction "PD1_P$27") (pintype "bidirectional"))
      (node (ref "GPS") (pin "P$9") (pinfunction "TX_P$9") (pintype "output"))
    )
    (net (code "34") (name "ISO_K") (class "Default")
      (node (ref "OBD_HDR") (pin "7") (pinfunction "7_7") (pintype "passive"))
    )
    (net (code "35") (name "ISO_L") (class "Default")
      (node (ref "OBD_HDR") (pin "8") (pinfunction "8_8") (pintype "passive"))
    )
    (net (code "36") (name "J1850+") (class "Default")
      (node (ref "OBD_HDR") (pin "9") (pinfunction "9_9") (pintype "passive"))
    )
    (net (code "37") (name "J1850-") (class "Default")
      (node (ref "OBD_HDR") (pin "10") (pinfunction "10_10") (pintype "passive"))
    )
    (net (code "38") (name "JTAG_TCK") (class "Default")
      (node (ref "AVR") (pin "P$12") (pinfunction "PB6_P$12") (pintype "bidirectional"))
      (node (ref "JTAG_HDR") (pin "1") (pinfunction "1_1") (pintype "passive"))
    )
    (net (code "39") (name "JTAG_TDI") (class "Default")
      (node (ref "AVR") (pin "P$11") (pinfunction "PB5_P$11") (pintype "bidirectional"))
      (node (ref "JTAG_HDR") (pin "9") (pinfunction "9_9") (pintype "passive"))
    )
    (net (code "40") (name "JTAG_TDO") (class "Default")
      (node (ref "AVR") (pin "P$13") (pinfunction "PB7_P$13") (pintype "bidirectional"))
      (node (ref "JTAG_HDR") (pin "3") (pinfunction "3_3") (pintype "passive"))
    )
    (net (code "41") (name "JTAG_TMS") (class "Default")
      (node (ref "AVR") (pin "P$10") (pinfunction "PB4_P$10") (pintype "bidirectional"))
      (node (ref "JTAG_HDR") (pin "5") (pinfunction "5_5") (pintype "passive"))
    )
    (net (code "42") (name "LCD_A0") (class "Default")
      (node (ref "AVR") (pin "P$18") (pinfunction "PC2_P$18") (pintype "bidirectional"))
      (node (ref "LCD_HDR") (pin "3") (pinfunction "3_3") (pintype "passive"))
    )
    (net (code "43") (name "LCD_BL_B-") (class "Default")
      (node (ref "LCD_HDR") (pin "11") (pinfunction "11_11") (pintype "passive"))
      (node (ref "R_BLU_LED") (pin "2") (pinfunction "2_2") (pintype "passive"))
    )
    (net (code "44") (name "LCD_BL_G-") (class "Default")
      (node (ref "LCD_HDR") (pin "10") (pinfunction "10_10") (pintype "passive"))
      (node (ref "R_GRN_LED") (pin "2") (pinfunction "2_2") (pintype "passive"))
    )
    (net (code "45") (name "LCD_BL_R-") (class "Default")
      (node (ref "LCD_HDR") (pin "8") (pinfunction "8_8") (pintype "passive"))
      (node (ref "R_RED_LED") (pin "2") (pinfunction "2_2") (pintype "passive"))
    )
    (net (code "46") (name "LCD_RESET") (class "Default")
      (node (ref "AVR") (pin "P$16") (pinfunction "PC0_P$16") (pintype "bidirectional"))
      (node (ref "LCD_HDR") (pin "2") (pinfunction "2_2") (pintype "passive"))
      (node (ref "R_LCD_RESET") (pin "1") (pinfunction "1_1") (pintype "passive"))
    )
    (net (code "47") (name "LCD_SCLK") (class "Default")
      (node (ref "AVR") (pin "P$17") (pinfunction "PC1_P$17") (pintype "bidirectional"))
      (node (ref "LCD_HDR") (pin "4") (pinfunction "4_4") (pintype "passive"))
    )
    (net (code "48") (name "LCD_SID") (class "Default")
      (node (ref "AVR") (pin "P$19") (pinfunction "PC3_P$19") (pintype "bidirectional"))
      (node (ref "LCD_HDR") (pin "5") (pinfunction "5_5") (pintype "passive"))
    )
    (net (code "49") (name "Net-(AVR-AVCC)") (class "Default")
      (node (ref "AVR") (pin "P$61") (pinfunction "AVCC_P$61") (pintype "power_in"))
      (node (ref "BEAD_AVR_ANALOG") (pin "1") (pinfunction "1_1") (pintype "passive"))
      (node (ref "C_AVR_ANALOG") (pin "1") (pinfunction "1_1") (pintype "passive"))
      (node (ref "C_AVR_ANALOG_LOCAL") (pin "+") (pinfunction "+_+") (pintype "passive"))
    )
    (net (code "50") (name "Net-(AVR-PDI)") (class "Default")
      (node (ref "AVR") (pin "P$56") (pinfunction "PDI_P$56") (pintype "bidirectional"))
      (node (ref "PDI_HDR") (pin "1") (pinfunction "1_1") (pintype "passive"))
    )
    (net (code "51") (name "Net-(AVR-PE0)") (class "Default")
      (node (ref "AVR") (pin "P$36") (pinfunction "PE0_P$36") (pintype "bidirectional"))
      (node (ref "NMOS_BLU") (pin "3") (pinfunction "G_3") (pintype "passive"))
      (node (ref "R_BLU_PD") (pin "2") (pinfunction "2_2") (pintype "passive"))
    )
    (net (code "52") (name "Net-(AVR-PE1)") (class "Default")
      (node (ref "AVR") (pin "P$37") (pinfunction "PE1_P$37") (pintype "bidirectional"))
      (node (ref "NMOS_GRN") (pin "3") (pinfunction "G_3") (pintype "passive"))
      (node (ref "R_GRN_PD") (pin "2") (pinfunction "2_2") (pintype "passive"))
    )
    (net (code "53") (name "Net-(AVR-PE2)") (class "Default")
      (node (ref "AVR") (pin "P$38") (pinfunction "PE2_P$38") (pintype "bidirectional"))
      (node (ref "NMOS_RED") (pin "3") (pinfunction "G_3") (pintype "passive"))
      (node (ref "R_RED_PD") (pin "2") (pinfunction "2_2") (pintype "passive"))
    )
    (net (code "54") (name "Net-(AVR-PR0)") (class "Default")
      (node (ref "AVR") (pin "P$58") (pinfunction "PR0_P$58") (pintype "bidirectional"))
      (node (ref "AVR_XTAL") (pin "1") (pinfunction "1_1") (pintype "passive"))
      (node (ref "C_AVR_XTAL1") (pin "1") (pinfunction "1_1") (pintype "passive"))
    )
    (net (code "55") (name "Net-(AVR-PR1)") (class "Default")
      (node (ref "AVR") (pin "P$59") (pinfunction "PR1_P$59") (pintype "bidirectional"))
      (node (ref "AVR_XTAL") (pin "2") (pinfunction "2_2") (pintype "passive"))
      (node (ref "C_AVR_XTAL2") (pin "1") (pinfunction "1_1") (pintype "passive"))
    )
    (net (code "56") (name "Net-(AVR-VCC-PadP$15)") (class "Default")
      (node (ref "AVR") (pin "P$15") (pinfunction "VCC_P$15") (pintype "power_in"))
      (node (ref "AVR") (pin "P$25") (pinfunction "VCC_P$25") (pintype "power_in"))
      (node (ref "AVR") (pin "P$35") (pinfunction "VCC_P$35") (pintype "power_in"))
      (node (ref "AVR") (pin "P$45") (pinfunction "VCC_P$45") (pintype "power_in"))
      (node (ref "AVR") (pin "P$53") (pinfunction "VCC_P$53") (pintype "power_in"))
      (node (ref "BEAD_AVR_ANALOG") (pin "2") (pinfunction "2_2") (pintype "passive"))
      (node (ref "C14") (pin "1") (pinfunction "1_1") (pintype "passive"))
      (node (ref "C15") (pin "1") (pinfunction "1_1") (pintype "passive"))
      (node (ref "C16") (pin "1") (pinfunction "1_1") (pintype "passive"))
      (node (ref "C17") (pin "1") (pinfunction "1_1") (pintype "passive"))
      (node (ref "C18") (pin "1") (pinfunction "1_1") (pintype "passive"))
      (node (ref "C_AVR_PWR") (pin "+") (pinfunction "+_+") (pintype "passive"))
      (node (ref "L_AVR_PWR") (pin "1") (pinfunction "1_1") (pintype "passive"))
    )
    (net (code "57") (name "Net-(CAN_CTRLR-OSC1)") (class "Default")
      (node (ref "CAN_CTRLR") (pin "P$9") (pinfunction "OSC1_P$9") (pintype "bidirectional"))
      (node (ref "CAN_XTAL") (pin "2") (pinfunction "2_2") (pintype "passive"))
      (node (ref "C_CAN_XTAL1") (pin "1") (pinfunction "1_1") (pintype "passive"))
    )
    (net (code "58") (name "Net-(CAN_CTRLR-OSC2)") (class "Default")
      (node (ref "CAN_CTRLR") (pin "P$8") (pinfunction "OSC2_P$8") (pintype "bidirectional"))
      (node (ref "CAN_XTAL") (pin "1") (pinfunction "1_1") (pintype "passive"))
      (node (ref "C_CAN_XTAL2") (pin "1") (pinfunction "1_1") (pintype "passive"))
    )
    (net (code "59") (name "Net-(CAN_CTRLR-{slash}RESET)") (class "Default")
      (node (ref "CAN_CTRLR") (pin "P$19") (pinfunction "/RESET_P$19") (pintype "bidirectional"))
      (node (ref "R_CAN_RST1") (pin "2") (pinfunction "2_2") (pintype "passive"))
    )
    (net (code "60") (name "Net-(C_CAN_RST-Pad1)") (class "Default")
      (node (ref "C_CAN_RST") (pin "1") (pinfunction "1_1") (pintype "passive"))
      (node (ref "R_CAN_RST1") (pin "1") (pinfunction "1_1") (pintype "passive"))
      (node (ref "R_CAN_RST2") (pin "1") (pinfunction "1_1") (pintype "passive"))
    )
    (net (code "61") (name "Net-(FTDI-3V3OUT)") (class "Default")
      (node (ref "C_FTDI_FLOAT") (pin "1") (pinfunction "1_1") (pintype "passive"))
      (node (ref "FTDI") (pin "P$13") (pinfunction "3V3OUT_P$13") (pintype "power_in"))
      (node (ref "FTDI") (pin "P$14") (pinfunction "RESET#_P$14") (pintype "bidirectional"))
      (node (ref "FTDI") (pin "P$3") (pinfunction "VCCIO_P$3") (pintype "power_in"))
    )
    (net (code "62") (name "Net-(FTDI-CBUS1)") (class "Default")
      (node (ref "FTDI") (pin "P$17") (pinfunction "CBUS1_P$17") (pintype "bidirectional"))
      (node (ref "R_FTDI_RX_LED") (pin "2") (pinfunction "2_2") (pintype "passive"))
    )
    (net (code "63") (name "Net-(FTDI-CBUS2)") (class "Default")
      (node (ref "FTDI") (pin "P$10") (pinfunction "CBUS2_P$10") (pintype "bidirectional"))
      (node (ref "R_FTDI_TX_LED") (pin "2") (pinfunction "2_2") (pintype "passive"))
    )
    (net (code "64") (name "Net-(FTDI-USBDM)") (class "Default")
      (node (ref "FTDI") (pin "P$12") (pinfunction "USBDM_P$12") (pintype "bidirectional"))
      (node (ref "R_USB-") (pin "1") (pinfunction "1_1") (pintype "passive"))
    )
    (net (code "65") (name "Net-(FTDI-USBDP)") (class "Default")
      (node (ref "FTDI") (pin "P$11") (pinfunction "USBDP_P$11") (pintype "bidirectional"))
      (node (ref "R_USB+") (pin "1") (pinfunction "1_1") (pintype "passive"))
    )
    (net (code "66") (name "Net-(FTDI_RX_LED-PadC)") (class "Default")
      (node (ref "FTDI_RX_LED") (pin "C") (pinfunction "C_C") (pintype "passive"))
      (node (ref "R_FTDI_RX_LED") (pin "1") (pinfunction "1_1") (pintype "passive"))
    )
    (net (code "67") (name "Net-(FTDI_TX_LED-PadC)") (class "Default")
      (node (ref "FTDI_TX_LED") (pin "C") (pinfunction "C_C") (pintype "passive"))
      (node (ref "R_FTDI_TX_LED") (pin "1") (pinfunction "1_1") (pintype "passive"))
    )
    (net (code "68") (name "Net-(GPS-VCC)") (class "Default")
      (node (ref "BEAD_GPS") (pin "2") (pinfunction "2_2") (pintype "passive"))
      (node (ref "C_GPS_PWR1") (pin "1") (pinfunction "1_1") (pintype "passive"))
      (node (ref "C_GPS_PWR2") (pin "+") (pinfunction "+_+") (pintype "passive"))
      (node (ref "GPS") (pin "P$1") (pinfunction "VCC_P$1") (pintype "power_in"))
    )
    (net (code "69") (name "Net-(MINIUSB-D+)") (class "Default")
      (node (ref "C_USB+") (pin "1") (pinfunction "1_1") (pintype "passive"))
      (node (ref "MINIUSB") (pin "P$3") (pinfunction "D+_P$3") (pintype "bidirectional"))
      (node (ref "R_USB+") (pin "2") (pinfunction "2_2") (pintype "passive"))
    )
    (net (code "70") (name "Net-(MINIUSB-D-)") (class "Default")
      (node (ref "C_USB-") (pin "1") (pinfunction "1_1") (pintype "passive"))
      (node (ref "MINIUSB") (pin "P$2") (pinfunction "D-_P$2") (pintype "bidirectional"))
      (node (ref "R_USB-") (pin "2") (pinfunction "2_2") (pintype "passive"))
    )
    (net (code "71") (name "Net-(MINIUSB-VBUS)") (class "Default")
      (node (ref "MINIUSB") (pin "P$1") (pinfunction "VBUS_P$1") (pintype "power_in"))
      (node (ref "R_VBUS_HIGH") (pin "2") (pinfunction "2_2") (pintype "passive"))
    )
    (net (code "72") (name "Net-(NMOS_BLU-S)") (class "Default")
      (node (ref "NMOS_BLU") (pin "2") (pinfunction "S_2") (pintype "passive"))
      (node (ref "R_BLU_LED") (pin "1") (pinfunction "1_1") (pintype "passive"))
    )
    (net (code "73") (name "Net-(NMOS_GRN-S)") (class "Default")
      (node (ref "NMOS_GRN") (pin "2") (pinfunction "S_2") (pintype "passive"))
      (node (ref "R_GRN_LED") (pin "1") (pinfunction "1_1") (pintype "passive"))
    )
    (net (code "74") (name "Net-(NMOS_RED-S)") (class "Default")
      (node (ref "NMOS_RED") (pin "2") (pinfunction "S_2") (pintype "passive"))
      (node (ref "R_RED_LED") (pin "1") (pinfunction "1_1") (pintype "passive"))
    )
    (net (code "75") (name "Net-(PWR_LED-PadC)") (class "Default")
      (node (ref "PWR_LED") (pin "C") (pinfunction "C_C") (pintype "passive"))
      (node (ref "R_PWR_LED") (pin "2") (pinfunction "2_2") (pintype "passive"))
    )
    (net (code "76") (name "Net-(RTC-X1)") (class "Default")
      (node (ref "C_RTC_XTAL2") (pin "1") (pinfunction "1_1") (pintype "passive"))
      (node (ref "RTC") (pin "P$1") (pinfunction "X1_P$1") (pintype "bidirectional"))
      (node (ref "RTC_XTAL") (pin "2") (pinfunction "2_2") (pintype "passive"))
    )
    (net (code "77") (name "Net-(RTC-X2)") (class "Default")
      (node (ref "C_RTC_XTAL1") (pin "1") (pinfunction "1_1") (pintype "passive"))
      (node (ref "RTC") (pin "P$2") (pinfunction "X2_P$2") (pintype "bidirectional"))
      (node (ref "RTC_XTAL") (pin "1") (pinfunction "1_1") (pintype "passive"))
    )
    (net (code "78") (name "RESET") (class "Default")
      (node (ref "AVR") (pin "P$57") (pinfunction "RESET_P$57") (pintype "bidirectional"))
      (node (ref "JTAG_HDR") (pin "6") (pinfunction "6_6") (pintype "passive"))
      (node (ref "PDI_HDR") (pin "5") (pinfunction "5_5") (pintype "passive"))
      (node (ref "R_RESET_PU") (pin "1") (pinfunction "1_1") (pintype "passive"))
      (node (ref "SW_RESET") (pin "1") (pinfunction "1_1") (pintype "passive"))
    )
    (net (code "79") (name "RTC_INT") (class "Default")
      (node (ref "AVR") (pin "P$47") (pinfunction "PF1_P$47") (pintype "bidirectional"))
      (node (ref "RTC") (pin "P$9") (pinfunction "SQW/INT_P$9") (pintype "output"))
      (node (ref "R_RTC_INT") (pin "1") (pinfunction "1_1") (pintype "passive"))
    )
    (net (code "80") (name "RTC_MISO") (class "Default")
      (node (ref "AVR") (pin "P$22") (pinfunction "PC6_P$22") (pintype "bidirectional"))
      (node (ref "RTC") (pin "P$7") (pinfunction "DOUT_P$7") (pintype "output"))
    )
    (net (code "81") (name "RTC_MOSI") (class "Default")
      (node (ref "AVR") (pin "P$21") (pinfunction "PC5_P$21") (pintype "bidirectional"))
      (node (ref "RTC") (pin "P$6") (pinfunction "DIN_P$6") (pintype "input"))
    )
    (net (code "82") (name "RTC_SCK") (class "Default")
      (node (ref "AVR") (pin "P$23") (pinfunction "PC7_P$23") (pintype "bidirectional"))
      (node (ref "RTC") (pin "P$8") (pinfunction "SCLK_P$8") (pintype "input"))
    )
    (net (code "83") (name "RTC_SS") (class "Default")
      (node (ref "AVR") (pin "P$20") (pinfunction "PC4_P$20") (pintype "bidirectional"))
      (node (ref "RTC") (pin "P$4") (pinfunction "/CS_P$4") (pintype "input"))
      (node (ref "R_RTC_SS") (pin "2") (pinfunction "2_2") (pintype "passive"))
    )
    (net (code "84") (name "SD_DAT1") (class "Default")
      (node (ref "AVR") (pin "P$6") (pinfunction "PB0_P$6") (pintype "bidirectional"))
      (node (ref "MICROSD") (pin "P$8") (pinfunction "NC/DAT1_P$8") (pintype "bidirectional"))
    )
    (net (code "85") (name "SD_DAT2") (class "Default")
      (node (ref "AVR") (pin "P$7") (pinfunction "PB1_P$7") (pintype "bidirectional"))
      (node (ref "MICROSD") (pin "P$1") (pinfunction "NC/DAT2_P$1") (pintype "bidirectional"))
    )
    (net (code "86") (name "SD_DETECT") (class "Default")
      (node (ref "AVR") (pin "P$39") (pinfunction "PE3_P$39") (pintype "bidirectional"))
      (node (ref "MICROSD") (pin "P$9") (pinfunction "DETECT_P$9") (pintype "bidirectional"))
      (node (ref "R_SD_DETECT") (pin "1") (pinfunction "1_1") (pintype "passive"))
    )
    (net (code "87") (name "SD_MISO") (class "Default")
      (node (ref "AVR") (pin "P$42") (pinfunction "PE6_P$42") (pintype "bidirectional"))
      (node (ref "MICROSD") (pin "P$7") (pinfunction "DO/DAT0_P$7") (pintype "output"))
    )
    (net (code "88") (name "SD_MOSI") (class "Default")
      (node (ref "AVR") (pin "P$41") (pinfunction "PE5_P$41") (pintype "bidirectional"))
      (node (ref "MICROSD") (pin "P$3") (pinfunction "DI/CMD_P$3") (pintype "input"))
    )
    (net (code "89") (name "SD_SCK") (class "Default")
      (node (ref "AVR") (pin "P$43") (pinfunction "PE7_P$43") (pintype "bidirectional"))
      (node (ref "MICROSD") (pin "P$5") (pinfunction "SCLK/CLK_P$5") (pintype "input"))
    )
    (net (code "90") (name "SD_SS") (class "Default")
      (node (ref "AVR") (pin "P$40") (pinfunction "PE4_P$40") (pintype "bidirectional"))
      (node (ref "MICROSD") (pin "P$2") (pinfunction "CS/DAT3_P$2") (pintype "input"))
      (node (ref "R_SD_SS") (pin "2") (pinfunction "2_2") (pintype "passive"))
    )
    (net (code "91") (name "VBACKUP") (class "Default")
      (node (ref "C_GPS_BATT") (pin "+") (pinfunction "+_+") (pintype "passive"))
      (node (ref "GPS") (pin "P$4") (pinfunction "VBACKUP_P$4") (pintype "power_in"))
      (node (ref "RTC") (pin "P$3") (pinfunction "VBACKUP_P$3") (pintype "power_in"))
      (node (ref "RTC_BATT") (pin "P$1") (pinfunction "+_P$1") (pintype "power_in"))
    )
    (net (code "92") (name "VBUS_SENSE") (class "Default")
      (node (ref "FTDI") (pin "P$18") (pinfunction "CBUS0_P$18") (pintype "bidirectional"))
      (node (ref "R_VBUS_HIGH") (pin "1") (pinfunction "1_1") (pintype "passive"))
      (node (ref "R_VBUS_LOW") (pin "2") (pinfunction "2_2") (pintype "passive"))
    )
    (net (code "93") (name "unconnected-(AVR-PB3-PadP$9)") (class "Default")
      (node (ref "AVR") (pin "P$9") (pinfunction "PB3_P$9") (pintype "bidirectional"))
    )
    (net (code "94") (name "unconnected-(AVR-PF0-PadP$46)") (class "Default")
      (node (ref "AVR") (pin "P$46") (pinfunction "PF0_P$46") (pintype "bidirectional"))
    )
    (net (code "95") (name "unconnected-(AVR-PF6-PadP$54)") (class "Default")
      (node (ref "AVR") (pin "P$54") (pinfunction "PF6_P$54") (pintype "bidirectional"))
    )
    (net (code "96") (name "unconnected-(AVR-PF7-PadP$55)") (class "Default")
      (node (ref "AVR") (pin "P$55") (pinfunction "PF7_P$55") (pintype "bidirectional"))
    )
    (net (code "97") (name "unconnected-(BTN_HDR-Pad9)") (class "Default")
      (node (ref "BTN_HDR") (pin "9") (pinfunction "9_9") (pintype "passive"))
    )
    (net (code "98") (name "unconnected-(CAN_CTRLR-CLKOUT{slash}SOF-PadP$3)") (class "Default")
      (node (ref "CAN_CTRLR") (pin "P$3") (pinfunction "CLKOUT/SOF_P$3") (pintype "bidirectional"))
    )
    (net (code "99") (name "unconnected-(CAN_CTRLR-{slash}RX0BF-PadP$12)") (class "Default")
      (node (ref "CAN_CTRLR") (pin "P$12") (pinfunction "/RX0BF_P$12") (pintype "bidirectional"))
    )
    (net (code "100") (name "unconnected-(CAN_CTRLR-{slash}RX1BF-PadP$11)") (class "Default")
      (node (ref "CAN_CTRLR") (pin "P$11") (pinfunction "/RX1BF_P$11") (pintype "bidirectional"))
    )
    (net (code "101") (name "unconnected-(CAN_CTRLR-{slash}TX0RTS-PadP$4)") (class "Default")
      (node (ref "CAN_CTRLR") (pin "P$4") (pinfunction "/TX0RTS_P$4") (pintype "bidirectional"))
    )
    (net (code "102") (name "unconnected-(CAN_CTRLR-{slash}TX1RTS-PadP$5)") (class "Default")
      (node (ref "CAN_CTRLR") (pin "P$5") (pinfunction "/TX1RTS_P$5") (pintype "bidirectional"))
    )
    (net (code "103") (name "unconnected-(CAN_CTRLR-{slash}TX2RTS-PadP$7)") (class "Default")
      (node (ref "CAN_CTRLR") (pin "P$7") (pinfunction "/TX2RTS_P$7") (pintype "bidirectional"))
    )
    (net (code "104") (name "unconnected-(FTDI-CBUS3-PadP$19)") (class "Default")
      (node (ref "FTDI") (pin "P$19") (pinfunction "CBUS3_P$19") (pintype "bidirectional"))
    )
    (net (code "105") (name "unconnected-(GPS-3D_FIX-PadP$5)") (class "Default")
      (node (ref "GPS") (pin "P$5") (pinfunction "3D_FIX_P$5") (pintype "bidirectional"))
    )
    (net (code "106") (name "unconnected-(GPS-EX_ANT-PadP$11)") (class "Default")
      (node (ref "GPS") (pin "P$11") (pinfunction "EX_ANT_P$11") (pintype "bidirectional"))
    )
    (net (code "107") (name "unconnected-(GPS-NRESET-PadP$2)") (class "Default")
      (node (ref "GPS") (pin "P$2") (pinfunction "NRESET_P$2") (pintype "bidirectional"))
    )
    (net (code "108") (name "unconnected-(GPS-RTCM-PadP$14)") (class "Default")
      (node (ref "GPS") (pin "P$14") (pinfunction "RTCM_P$14") (pintype "bidirectional"))
    )
    (net (code "109") (name "unconnected-(JTAG_HDR-Pad7)") (class "Default")
      (node (ref "JTAG_HDR") (pin "7") (pinfunction "7_7") (pintype "passive"))
    )
    (net (code "110") (name "unconnected-(JTAG_HDR-Pad8)") (class "Default")
      (node (ref "JTAG_HDR") (pin "8") (pinfunction "8_8") (pintype "passive"))
    )
    (net (code "111") (name "unconnected-(LCD_HDR-Pad12)") (class "Default")
      (node (ref "LCD_HDR") (pin "12") (pinfunction "12_12") (pintype "passive"))
    )
    (net (code "112") (name "unconnected-(MINIUSB-ID-PadP$4)") (class "Default")
      (node (ref "MINIUSB") (pin "P$4") (pinfunction "ID_P$4") (pintype "bidirectional"))
    )
    (net (code "113") (name "unconnected-(OBD_HDR-Pad2)") (class "Default")
      (node (ref "OBD_HDR") (pin "2") (pinfunction "2_2") (pintype "passive"))
    )
    (net (code "114") (name "unconnected-(OBD_HDR-Pad4)") (class "Default")
      (node (ref "OBD_HDR") (pin "4") (pinfunction "4_4") (pintype "passive"))
    )
    (net (code "115") (name "unconnected-(PDI_HDR-Pad3)") (class "Default")
      (node (ref "PDI_HDR") (pin "3") (pinfunction "3_3") (pintype "passive"))
    )
    (net (code "116") (name "unconnected-(PDI_HDR-Pad4)") (class "Default")
      (node (ref "PDI_HDR") (pin "4") (pinfunction "4_4") (pintype "passive"))
    )
    (net (code "117") (name "unconnected-(SW_RESET-Pad2)") (class "Default")
      (node (ref "SW_RESET") (pin "2") (pinfunction "2_2") (pintype "passive"))
    )
    (net (code "118") (name "unconnected-(SW_RESET-Pad4)") (class "Default")
      (node (ref "SW_RESET") (pin "4") (pinfunction "4_4") (pintype "passive"))
    )
  )
)
